# ADC_Temp.net
KiCad netlist of a schematic drawn in Altium Designer
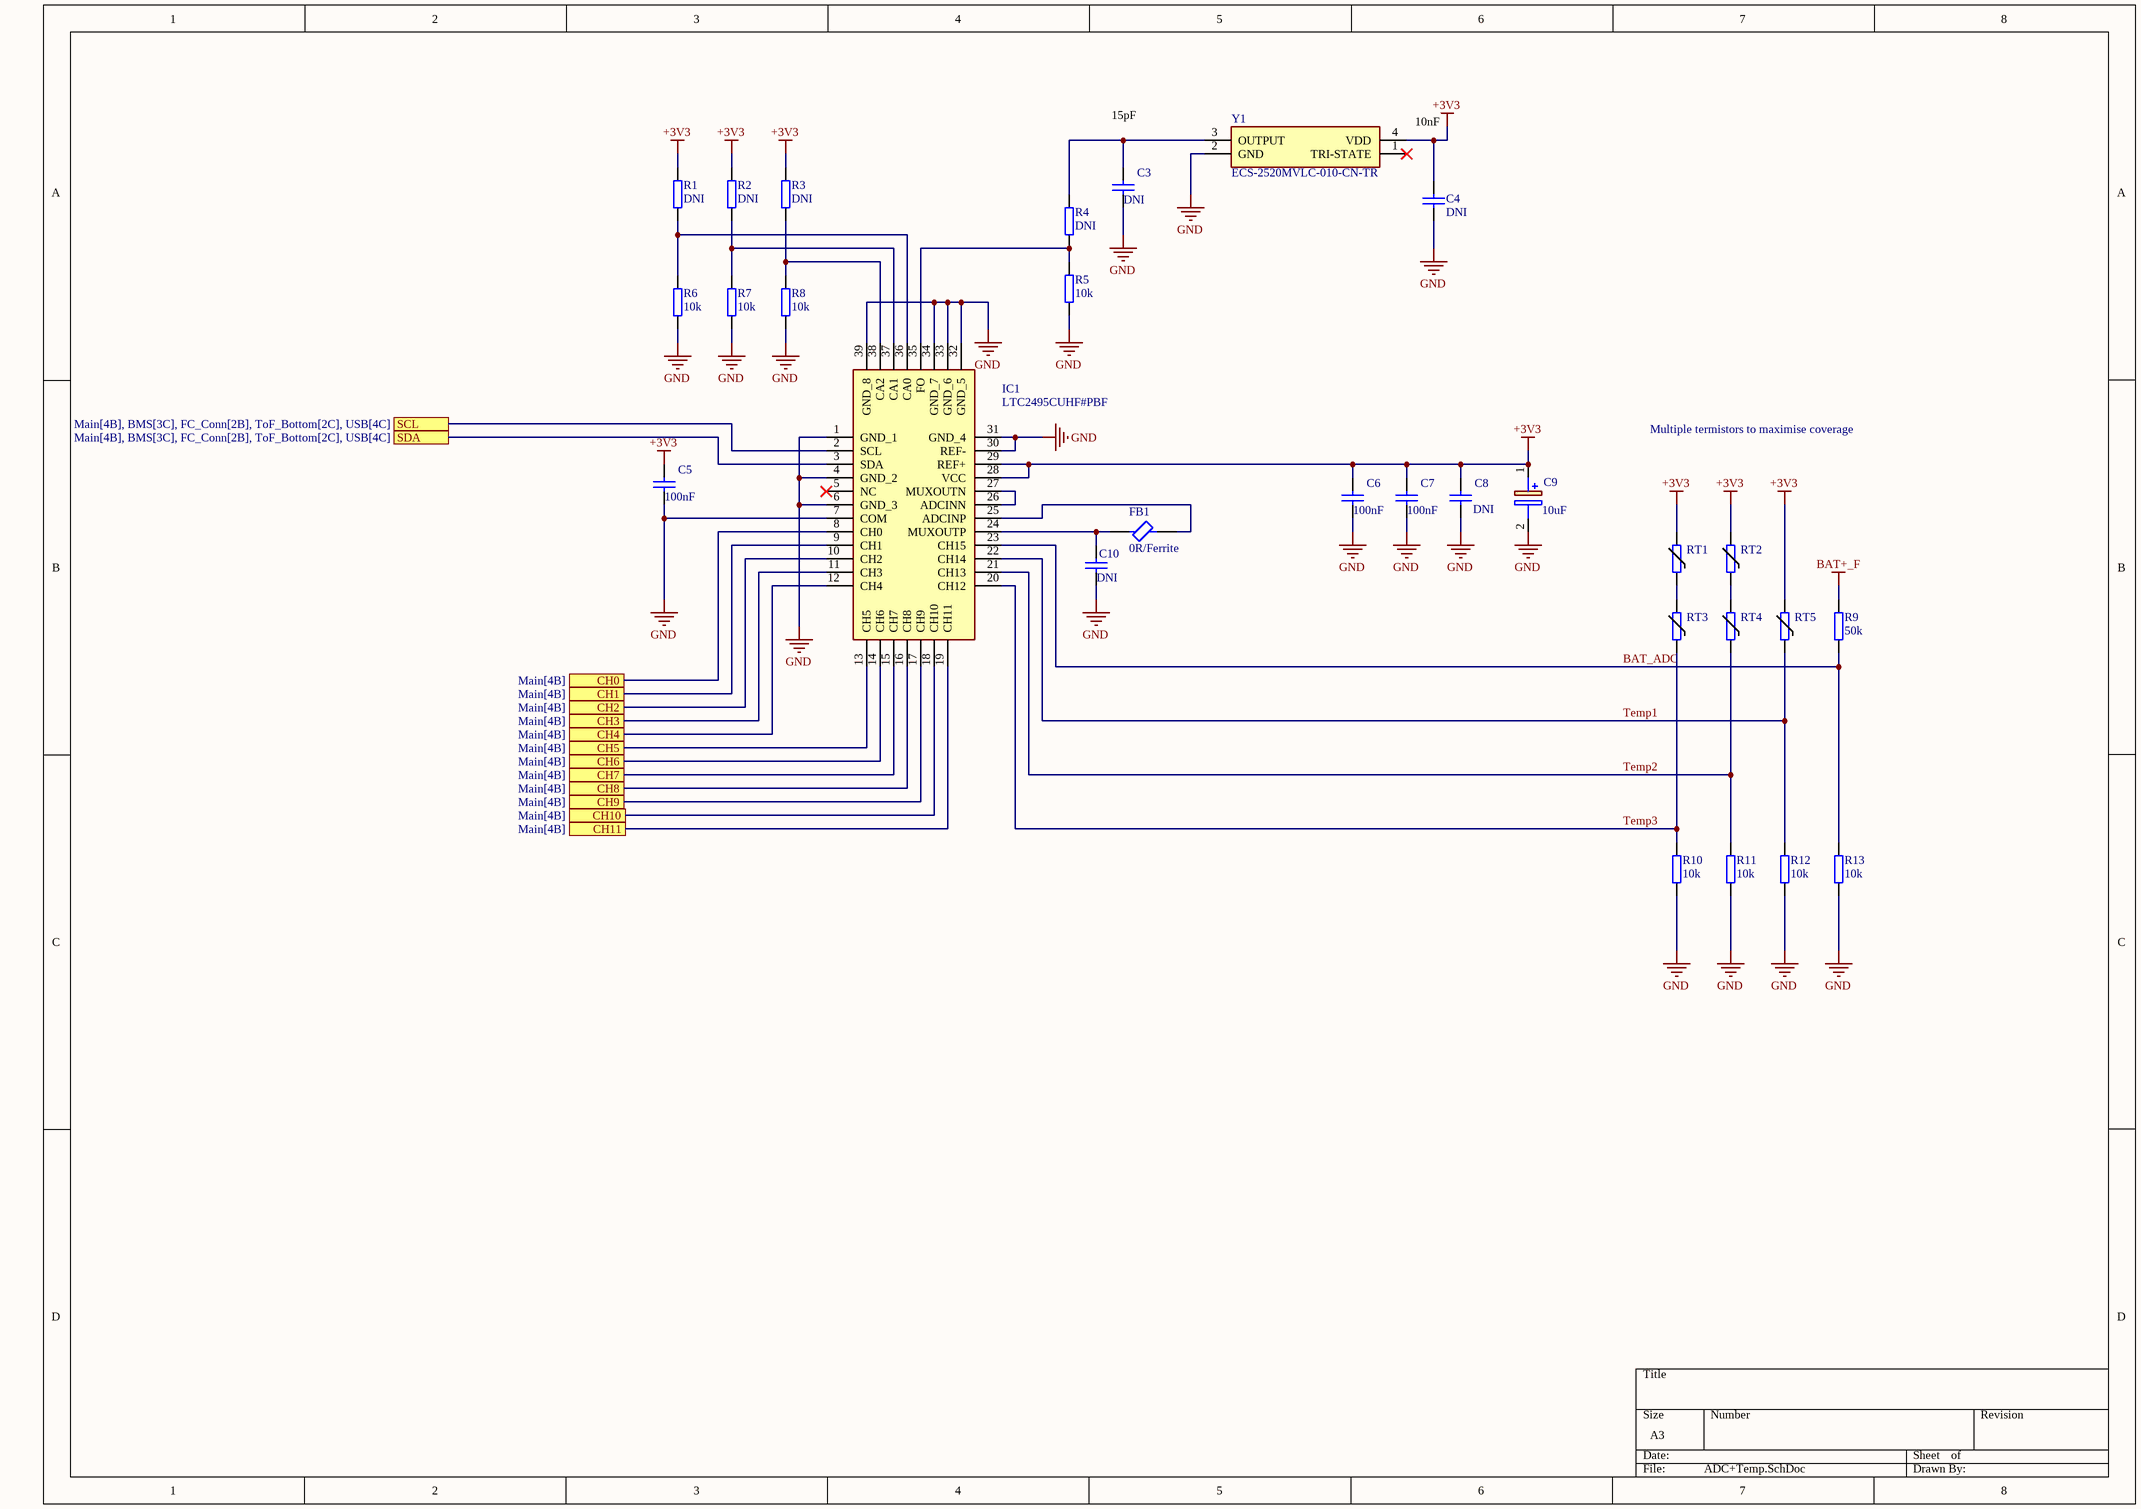
[diagram p0: ADC+Temp.SchDoc]

(export (version "E")
  (design (tool "Eeschema 10.0.6"))
  (components
    (comp (ref "C3")
      (value "DNI")
      (footprint "CAP0402")
      (fields (field (name "Comment") "Cap0402"))
      (libsource (lib "capacitorsSMD") (part "Cap0402"))
    )
    (comp (ref "C4")
      (value "DNI")
      (footprint "CAP0402")
      (fields (field (name "Comment") "Cap0402"))
      (libsource (lib "capacitorsSMD") (part "Cap0402"))
    )
    (comp (ref "C5")
      (value "100nF")
      (footprint "CAP0402")
      (fields
        (field (name "VOLTAGE") "50V")
        (field (name "MANUFACTURER_PART_NUMBER") "GRM155R71H104ME14D")
        (field (name "Comment") "Cap0402")
      )
      (libsource (lib "capacitorsSMD") (part "Cap0402"))
    )
    (comp (ref "C6")
      (value "100nF")
      (footprint "CAP0402")
      (fields
        (field (name "VOLTAGE") "50V")
        (field (name "MANUFACTURER_PART_NUMBER") "GRM155R71H104ME14D")
        (field (name "Comment") "Cap0402")
      )
      (libsource (lib "capacitorsSMD") (part "Cap0402"))
    )
    (comp (ref "C7")
      (value "100nF")
      (footprint "CAP0402")
      (fields
        (field (name "VOLTAGE") "50V")
        (field (name "MANUFACTURER_PART_NUMBER") "GRM155R71H104ME14D")
        (field (name "Comment") "Cap0402")
      )
      (libsource (lib "capacitorsSMD") (part "Cap0402"))
    )
    (comp (ref "C8")
      (value "DNI")
      (footprint "CAP0603")
      (fields (field (name "Comment") "Cap0603"))
      (libsource (lib "capacitorsSMD") (part "Cap0603"))
    )
    (comp (ref "C9")
      (value "10uF")
      (footprint "SamacSys:CAPPC1608X90N")
      (description "Capacitor Polarised")
      (fields (field (name "VOLTAGE") "6V3") (field (name "MANUFACTURER_PART_NUMBER") "TMCJ0J106MTRF"))
      (libsource (lib "*") (part "298D106X96R3M2T"))
    )
    (comp (ref "C10")
      (value "DNI")
      (footprint "CAP0402")
      (fields (field (name "Comment") "Cap0402"))
      (libsource (lib "capacitorsSMD") (part "Cap0402"))
    )
    (comp (ref "FB1")
      (value "0R/Ferrite")
      (footprint "SamacSys:NFZ15SG152SN10B")
      (description "Ferrite Bead")
      (fields
        (field (name "MANUFACTURER_PART_NUMBER") "BLM15PE471SH1D")
        (field (name "MOUSER PART NUMBER") "81-BLM15PE471SH1D")
      )
      (libsource (lib "SamacSys") (part "BLM15PE471SH1D"))
    )
    (comp (ref "IC1")
      (value "LTC2495CUHF#PBF")
      (footprint "SamacSys:QFN50P500X700X80-39N-D")
      (description "Integrated Circuit")
      (fields (field (name "MOUSER PART NUMBER") "584-LTC2495CUHF#PBF"))
      (libsource (lib "*") (part "LTC2495CUHF#PBF"))
    )
    (comp (ref "R1")
      (value "DNI")
      (footprint "RES0402")
      (fields (field (name "Comment") "Res0402"))
      (libsource (lib "resistorSMD") (part "Res0402"))
    )
    (comp (ref "R2")
      (value "DNI")
      (footprint "RES0402")
      (fields (field (name "Comment") "Res0402"))
      (libsource (lib "resistorSMD") (part "Res0402"))
    )
    (comp (ref "R3")
      (value "DNI")
      (footprint "RES0402")
      (fields (field (name "Comment") "Res0402"))
      (libsource (lib "resistorSMD") (part "Res0402"))
    )
    (comp (ref "R4")
      (value "DNI")
      (footprint "RES0402")
      (fields (field (name "Comment") "Res0402"))
      (libsource (lib "resistorSMD") (part "Res0402"))
    )
    (comp (ref "R5")
      (value "10k")
      (footprint "RES0402")
      (fields (field (name "MANUFACTURER_PART_NUMBER") "ERA-2AED103X") (field (name "Comment") "Res0402"))
      (libsource (lib "resistorSMD") (part "Res0402"))
    )
    (comp (ref "R6")
      (value "10k")
      (footprint "RES0402")
      (fields (field (name "MANUFACTURER_PART_NUMBER") "ERA-2AED103X") (field (name "Comment") "Res0402"))
      (libsource (lib "resistorSMD") (part "Res0402"))
    )
    (comp (ref "R7")
      (value "10k")
      (footprint "RES0402")
      (fields (field (name "MANUFACTURER_PART_NUMBER") "ERA-2AED103X") (field (name "Comment") "Res0402"))
      (libsource (lib "resistorSMD") (part "Res0402"))
    )
    (comp (ref "R8")
      (value "10k")
      (footprint "RES0402")
      (fields (field (name "MANUFACTURER_PART_NUMBER") "ERA-2AED103X") (field (name "Comment") "Res0402"))
      (libsource (lib "resistorSMD") (part "Res0402"))
    )
    (comp (ref "R9")
      (value "50k")
      (footprint "RES0402")
      (fields (field (name "MANUFACTURER_PART_NUMBER") "TNPW040249K9DEED") (field (name "Comment") "Res0402"))
      (libsource (lib "resistorSMD") (part "Res0402"))
    )
    (comp (ref "R10")
      (value "10k")
      (footprint "RES0402")
      (fields (field (name "MANUFACTURER_PART_NUMBER") "ERA-2AED103X") (field (name "Comment") "Res0402"))
      (libsource (lib "resistorSMD") (part "Res0402"))
    )
    (comp (ref "R11")
      (value "10k")
      (footprint "RES0402")
      (fields (field (name "MANUFACTURER_PART_NUMBER") "ERA-2AED103X") (field (name "Comment") "Res0402"))
      (libsource (lib "resistorSMD") (part "Res0402"))
    )
    (comp (ref "R12")
      (value "10k")
      (footprint "RES0402")
      (fields (field (name "MANUFACTURER_PART_NUMBER") "ERA-2AED103X") (field (name "Comment") "Res0402"))
      (libsource (lib "resistorSMD") (part "Res0402"))
    )
    (comp (ref "R13")
      (value "10k")
      (footprint "RES0402")
      (fields (field (name "MANUFACTURER_PART_NUMBER") "ERA-2AED103X") (field (name "Comment") "Res0402"))
      (libsource (lib "resistorSMD") (part "Res0402"))
    )
    (comp (ref "RT1")
      (value "TMP6131DECR")
      (footprint "SamacSys:TMP6131DECR")
      (description "Integrated Circuit")
      (fields (field (name "MOUSER PART NUMBER") "595-TMP6131DECR"))
      (libsource (lib "SamacSys") (part "TMP6131DECR"))
    )
    (comp (ref "RT2")
      (value "TMP6131DECR")
      (footprint "SamacSys:TMP6131DECR")
      (description "Integrated Circuit")
      (fields (field (name "MOUSER PART NUMBER") "595-TMP6131DECR"))
      (libsource (lib "SamacSys") (part "TMP6131DECR"))
    )
    (comp (ref "RT3")
      (value "TMP6131DECR")
      (footprint "SamacSys:TMP6131DECR")
      (description "Integrated Circuit")
      (fields (field (name "MOUSER PART NUMBER") "595-TMP6131DECR"))
      (libsource (lib "SamacSys") (part "TMP6131DECR"))
    )
    (comp (ref "RT4")
      (value "TMP6131DECR")
      (footprint "SamacSys:TMP6131DECR")
      (description "Integrated Circuit")
      (fields (field (name "MOUSER PART NUMBER") "595-TMP6131DECR"))
      (libsource (lib "SamacSys") (part "TMP6131DECR"))
    )
    (comp (ref "RT5")
      (value "TMP6131DECR")
      (footprint "SamacSys:TMP6131DECR")
      (description "Integrated Circuit")
      (fields (field (name "MOUSER PART NUMBER") "595-TMP6131DECR"))
      (libsource (lib "SamacSys") (part "TMP6131DECR"))
    )
    (comp (ref "Y1")
      (value "ECS-2520MVLC-010-CN-TR")
      (footprint "SamacSys:ECS2520MVLC010CNTR")
      (description "Crystal or Oscillator")
      (fields (field (name "MOUSER PART NUMBER") "520-2520MVLC-010CNTR"))
      (libsource (lib "*") (part "ECS-2520MVLC-010-CN-TR"))
    )
  )
  (nets
    (net (code "1") (name "+3V3") (class "Default")
      (node (ref "C4") (pin "2") (pinfunction "2_2") (pintype "passive"))
      (node (ref "C5") (pin "2") (pinfunction "2_2") (pintype "passive"))
      (node (ref "C6") (pin "2") (pinfunction "2_2") (pintype "passive"))
      (node (ref "C7") (pin "2") (pinfunction "2_2") (pintype "passive"))
      (node (ref "C8") (pin "2") (pinfunction "2_2") (pintype "passive"))
      (node (ref "C9") (pin "1") (pinfunction "+_1") (pintype "passive"))
      (node (ref "IC1") (pin "28") (pinfunction "VCC_28") (pintype "passive"))
      (node (ref "IC1") (pin "29") (pinfunction "REF+_29") (pintype "passive"))
      (node (ref "R1") (pin "2") (pinfunction "2_2") (pintype "passive"))
      (node (ref "R2") (pin "2") (pinfunction "2_2") (pintype "passive"))
      (node (ref "R3") (pin "2") (pinfunction "2_2") (pintype "passive"))
      (node (ref "RT1") (pin "2") (pinfunction "2_2") (pintype "passive"))
      (node (ref "RT2") (pin "2") (pinfunction "2_2") (pintype "passive"))
      (node (ref "RT5") (pin "2") (pinfunction "2_2") (pintype "passive"))
      (node (ref "Y1") (pin "4") (pinfunction "VDD_4") (pintype "passive"))
    )
    (net (code "2") (name "/BAT_ADC") (class "Default")
      (node (ref "IC1") (pin "23") (pinfunction "CH15_23") (pintype "passive"))
      (node (ref "R13") (pin "2") (pinfunction "2_2") (pintype "passive"))
      (node (ref "R9") (pin "1") (pinfunction "1_1") (pintype "passive"))
    )
    (net (code "3") (name "/CH0") (class "Default")
      (node (ref "IC1") (pin "8") (pinfunction "CH0_8") (pintype "passive"))
    )
    (net (code "4") (name "/CH1") (class "Default")
      (node (ref "IC1") (pin "9") (pinfunction "CH1_9") (pintype "passive"))
    )
    (net (code "5") (name "/CH2") (class "Default")
      (node (ref "IC1") (pin "10") (pinfunction "CH2_10") (pintype "passive"))
    )
    (net (code "6") (name "/CH3") (class "Default")
      (node (ref "IC1") (pin "11") (pinfunction "CH3_11") (pintype "passive"))
    )
    (net (code "7") (name "/CH4") (class "Default")
      (node (ref "IC1") (pin "12") (pinfunction "CH4_12") (pintype "passive"))
    )
    (net (code "8") (name "/CH5") (class "Default")
      (node (ref "IC1") (pin "13") (pinfunction "CH5_13") (pintype "passive"))
    )
    (net (code "9") (name "/CH6") (class "Default")
      (node (ref "IC1") (pin "14") (pinfunction "CH6_14") (pintype "passive"))
    )
    (net (code "10") (name "/CH7") (class "Default")
      (node (ref "IC1") (pin "15") (pinfunction "CH7_15") (pintype "passive"))
    )
    (net (code "11") (name "/CH8") (class "Default")
      (node (ref "IC1") (pin "16") (pinfunction "CH8_16") (pintype "passive"))
    )
    (net (code "12") (name "/CH9") (class "Default")
      (node (ref "IC1") (pin "17") (pinfunction "CH9_17") (pintype "passive"))
    )
    (net (code "13") (name "/CH10") (class "Default")
      (node (ref "IC1") (pin "18") (pinfunction "CH10_18") (pintype "passive"))
    )
    (net (code "14") (name "/CH11") (class "Default")
      (node (ref "IC1") (pin "19") (pinfunction "CH11_19") (pintype "passive"))
    )
    (net (code "15") (name "/SCL") (class "Default")
      (node (ref "IC1") (pin "2") (pinfunction "SCL_2") (pintype "passive"))
    )
    (net (code "16") (name "/SDA") (class "Default")
      (node (ref "IC1") (pin "3") (pinfunction "SDA_3") (pintype "passive"))
    )
    (net (code "17") (name "/Temp1") (class "Default")
      (node (ref "IC1") (pin "22") (pinfunction "CH14_22") (pintype "passive"))
      (node (ref "R12") (pin "2") (pinfunction "2_2") (pintype "passive"))
      (node (ref "RT5") (pin "1") (pinfunction "1_1") (pintype "passive"))
    )
    (net (code "18") (name "/Temp2") (class "Default")
      (node (ref "IC1") (pin "21") (pinfunction "CH13_21") (pintype "passive"))
      (node (ref "R11") (pin "2") (pinfunction "2_2") (pintype "passive"))
      (node (ref "RT4") (pin "1") (pinfunction "1_1") (pintype "passive"))
    )
    (net (code "19") (name "/Temp3") (class "Default")
      (node (ref "IC1") (pin "20") (pinfunction "CH12_20") (pintype "passive"))
      (node (ref "R10") (pin "2") (pinfunction "2_2") (pintype "passive"))
      (node (ref "RT3") (pin "1") (pinfunction "1_1") (pintype "passive"))
    )
    (net (code "20") (name "BAT+_F") (class "Default")
      (node (ref "R9") (pin "2") (pinfunction "2_2") (pintype "passive"))
    )
    (net (code "21") (name "GND") (class "Default")
      (node (ref "C10") (pin "1") (pinfunction "1_1") (pintype "passive"))
      (node (ref "C3") (pin "1") (pinfunction "1_1") (pintype "passive"))
      (node (ref "C4") (pin "1") (pinfunction "1_1") (pintype "passive"))
      (node (ref "C5") (pin "1") (pinfunction "1_1") (pintype "passive"))
      (node (ref "C6") (pin "1") (pinfunction "1_1") (pintype "passive"))
      (node (ref "C7") (pin "1") (pinfunction "1_1") (pintype "passive"))
      (node (ref "C8") (pin "1") (pinfunction "1_1") (pintype "passive"))
      (node (ref "C9") (pin "2") (pinfunction "-_2") (pintype "passive"))
      (node (ref "IC1") (pin "1") (pinfunction "GND_1_1") (pintype "passive"))
      (node (ref "IC1") (pin "30") (pinfunction "REF-_30") (pintype "passive"))
      (node (ref "IC1") (pin "31") (pinfunction "GND_4_31") (pintype "passive"))
      (node (ref "IC1") (pin "32") (pinfunction "GND_5_32") (pintype "passive"))
      (node (ref "IC1") (pin "33") (pinfunction "GND_6_33") (pintype "passive"))
      (node (ref "IC1") (pin "34") (pinfunction "GND_7_34") (pintype "passive"))
      (node (ref "IC1") (pin "39") (pinfunction "GND_8_39") (pintype "passive"))
      (node (ref "IC1") (pin "4") (pinfunction "GND_2_4") (pintype "passive"))
      (node (ref "IC1") (pin "6") (pinfunction "GND_3_6") (pintype "passive"))
      (node (ref "IC1") (pin "7") (pinfunction "COM_7") (pintype "passive"))
      (node (ref "R10") (pin "1") (pinfunction "1_1") (pintype "passive"))
      (node (ref "R11") (pin "1") (pinfunction "1_1") (pintype "passive"))
      (node (ref "R12") (pin "1") (pinfunction "1_1") (pintype "passive"))
      (node (ref "R13") (pin "1") (pinfunction "1_1") (pintype "passive"))
      (node (ref "R5") (pin "1") (pinfunction "1_1") (pintype "passive"))
      (node (ref "R6") (pin "1") (pinfunction "1_1") (pintype "passive"))
      (node (ref "R7") (pin "1") (pinfunction "1_1") (pintype "passive"))
      (node (ref "R8") (pin "1") (pinfunction "1_1") (pintype "passive"))
      (node (ref "Y1") (pin "2") (pinfunction "GND_2") (pintype "passive"))
    )
    (net (code "22") (name "Net-(IC1-ADCINN)") (class "Default")
      (node (ref "IC1") (pin "26") (pinfunction "ADCINN_26") (pintype "passive"))
      (node (ref "IC1") (pin "27") (pinfunction "MUXOUTN_27") (pintype "passive"))
    )
    (net (code "23") (name "Net-(IC1-ADCINP)") (class "Default")
      (node (ref "FB1") (pin "2") (pinfunction "2_2") (pintype "passive"))
      (node (ref "IC1") (pin "25") (pinfunction "ADCINP_25") (pintype "passive"))
    )
    (net (code "24") (name "Net-(IC1-CA0)") (class "Default")
      (node (ref "IC1") (pin "36") (pinfunction "CA0_36") (pintype "passive"))
      (node (ref "R1") (pin "1") (pinfunction "1_1") (pintype "passive"))
      (node (ref "R6") (pin "2") (pinfunction "2_2") (pintype "passive"))
    )
    (net (code "25") (name "Net-(IC1-CA1)") (class "Default")
      (node (ref "IC1") (pin "37") (pinfunction "CA1_37") (pintype "passive"))
      (node (ref "R2") (pin "1") (pinfunction "1_1") (pintype "passive"))
      (node (ref "R7") (pin "2") (pinfunction "2_2") (pintype "passive"))
    )
    (net (code "26") (name "Net-(IC1-CA2)") (class "Default")
      (node (ref "IC1") (pin "38") (pinfunction "CA2_38") (pintype "passive"))
      (node (ref "R3") (pin "1") (pinfunction "1_1") (pintype "passive"))
      (node (ref "R8") (pin "2") (pinfunction "2_2") (pintype "passive"))
    )
    (net (code "27") (name "Net-(IC1-FO)") (class "Default")
      (node (ref "IC1") (pin "35") (pinfunction "FO_35") (pintype "passive"))
      (node (ref "R4") (pin "1") (pinfunction "1_1") (pintype "passive"))
      (node (ref "R5") (pin "2") (pinfunction "2_2") (pintype "passive"))
    )
    (net (code "28") (name "Net-(IC1-MUXOUTP)") (class "Default")
      (node (ref "C10") (pin "2") (pinfunction "2_2") (pintype "passive"))
      (node (ref "FB1") (pin "1") (pinfunction "1_1") (pintype "passive"))
      (node (ref "IC1") (pin "24") (pinfunction "MUXOUTP_24") (pintype "passive"))
    )
    (net (code "29") (name "Net-(RT1-Pad1)") (class "Default")
      (node (ref "RT1") (pin "1") (pinfunction "1_1") (pintype "passive"))
      (node (ref "RT3") (pin "2") (pinfunction "2_2") (pintype "passive"))
    )
    (net (code "30") (name "Net-(RT2-Pad1)") (class "Default")
      (node (ref "RT2") (pin "1") (pinfunction "1_1") (pintype "passive"))
      (node (ref "RT4") (pin "2") (pinfunction "2_2") (pintype "passive"))
    )
    (net (code "31") (name "Net-(Y1-OUTPUT)") (class "Default")
      (node (ref "C3") (pin "2") (pinfunction "2_2") (pintype "passive"))
      (node (ref "R4") (pin "2") (pinfunction "2_2") (pintype "passive"))
      (node (ref "Y1") (pin "3") (pinfunction "OUTPUT_3") (pintype "passive"))
    )
    (net (code "32") (name "unconnected-(IC1-NC-Pad5)") (class "Default")
      (node (ref "IC1") (pin "5") (pinfunction "NC_5") (pintype "passive+no_connect"))
    )
    (net (code "33") (name "unconnected-(Y1-TRI-STATE-Pad1)") (class "Default")
      (node (ref "Y1") (pin "1") (pinfunction "TRI-STATE_1") (pintype "passive+no_connect"))
    )
  )
)
